# MCU_POWER.net
KiCad netlist of a schematic drawn in Altium Designer
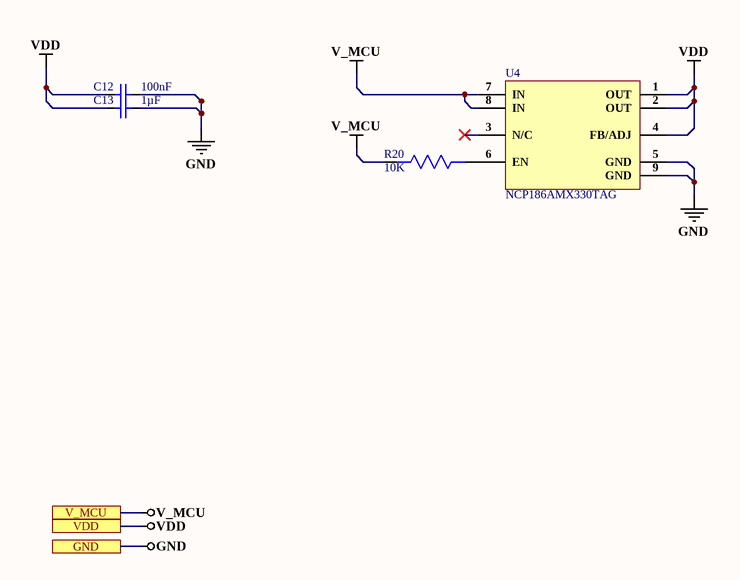
[diagram p0: MCU_POWER.SchDoc]

(export (version "E")
  (design (tool "Eeschema 10.0.6"))
  (components
    (comp (ref "C12")
      (value "100nF")
      (footprint "Cap0402")
      (description "CAP CER 0.1UF 25V X7R 0402")
      (fields
        (field (name "MANUFACTURER") "Yageo")
        (field (name "MANUFACTURER PART NUMBER") "CC0402KRX7R8BB104")
      )
      (libsource (lib "TT_IntLib") (part "CC0402KRX7R8BB104"))
    )
    (comp (ref "C13")
      (value "1µF")
      (footprint "Cap0402")
      (description "CAP CER 1UF 25V X5R 0402")
      (fields
        (field (name "MANUFACTURER") "Murata")
        (field (name "MANUFACTURER PART NUMBER") "GRM155R61E105KA12D")
      )
      (libsource (lib "TT_IntLib") (part "GRM155R61E105KA12D"))
    )
    (comp (ref "R20")
      (value "10K")
      (footprint "Res-0201")
      (description "GENERAL 0201 11% REEL (7INCH)")
      (fields
        (field (name "MANUFACTURER") "Yageo")
        (field (name "MANUFACTURER PART NUMBER") "RC0201FR-0710KL")
      )
      (libsource (lib "TT_IntLib") (part "RC0201FR-0710KL"))
    )
    (comp (ref "U4")
      (value "NCP186AMX330TAG")
      (footprint "NCP186AMX330TAG")
      (description "IC REG LINEAR 3.3V 1A 8XDFN")
      (fields (field (name "MANUFACTURER") "ON Semiconductor"))
      (libsource (lib "TT_IntLib") (part "NCP186AMX330TAG"))
    )
  )
  (nets
    (net (code "1") (name "GND") (class "Default")
      (node (ref "C12") (pin "1") (pintype "passive"))
      (node (ref "C13") (pin "1") (pintype "passive"))
      (node (ref "U4") (pin "5") (pinfunction "GND_5") (pintype "power_in"))
      (node (ref "U4") (pin "9") (pinfunction "GND_9") (pintype "power_in"))
    )
    (net (code "2") (name "Net-(U4-EN)") (class "Default")
      (node (ref "R20") (pin "1") (pintype "passive"))
      (node (ref "U4") (pin "6") (pinfunction "EN_6") (pintype "passive"))
    )
    (net (code "3") (name "VDD") (class "Default")
      (node (ref "C12") (pin "2") (pintype "passive"))
      (node (ref "C13") (pin "2") (pintype "passive"))
      (node (ref "U4") (pin "1") (pinfunction "OUT_1") (pintype "passive"))
      (node (ref "U4") (pin "2") (pinfunction "OUT_2") (pintype "passive"))
      (node (ref "U4") (pin "4") (pinfunction "FB/ADJ_4") (pintype "passive"))
    )
    (net (code "4") (name "V_MCU") (class "Default")
      (node (ref "R20") (pin "2") (pintype "passive"))
      (node (ref "U4") (pin "7") (pinfunction "IN_7") (pintype "passive"))
      (node (ref "U4") (pin "8") (pinfunction "IN_8") (pintype "passive"))
    )
    (net (code "5") (name "unconnected-(U4-N{slash}C-Pad3)") (class "Default")
      (node (ref "U4") (pin "3") (pinfunction "N/C_3") (pintype "passive+no_connect"))
    )
  )
)
